# first.net
KiCad netlist of a schematic drawn in EasyEDA
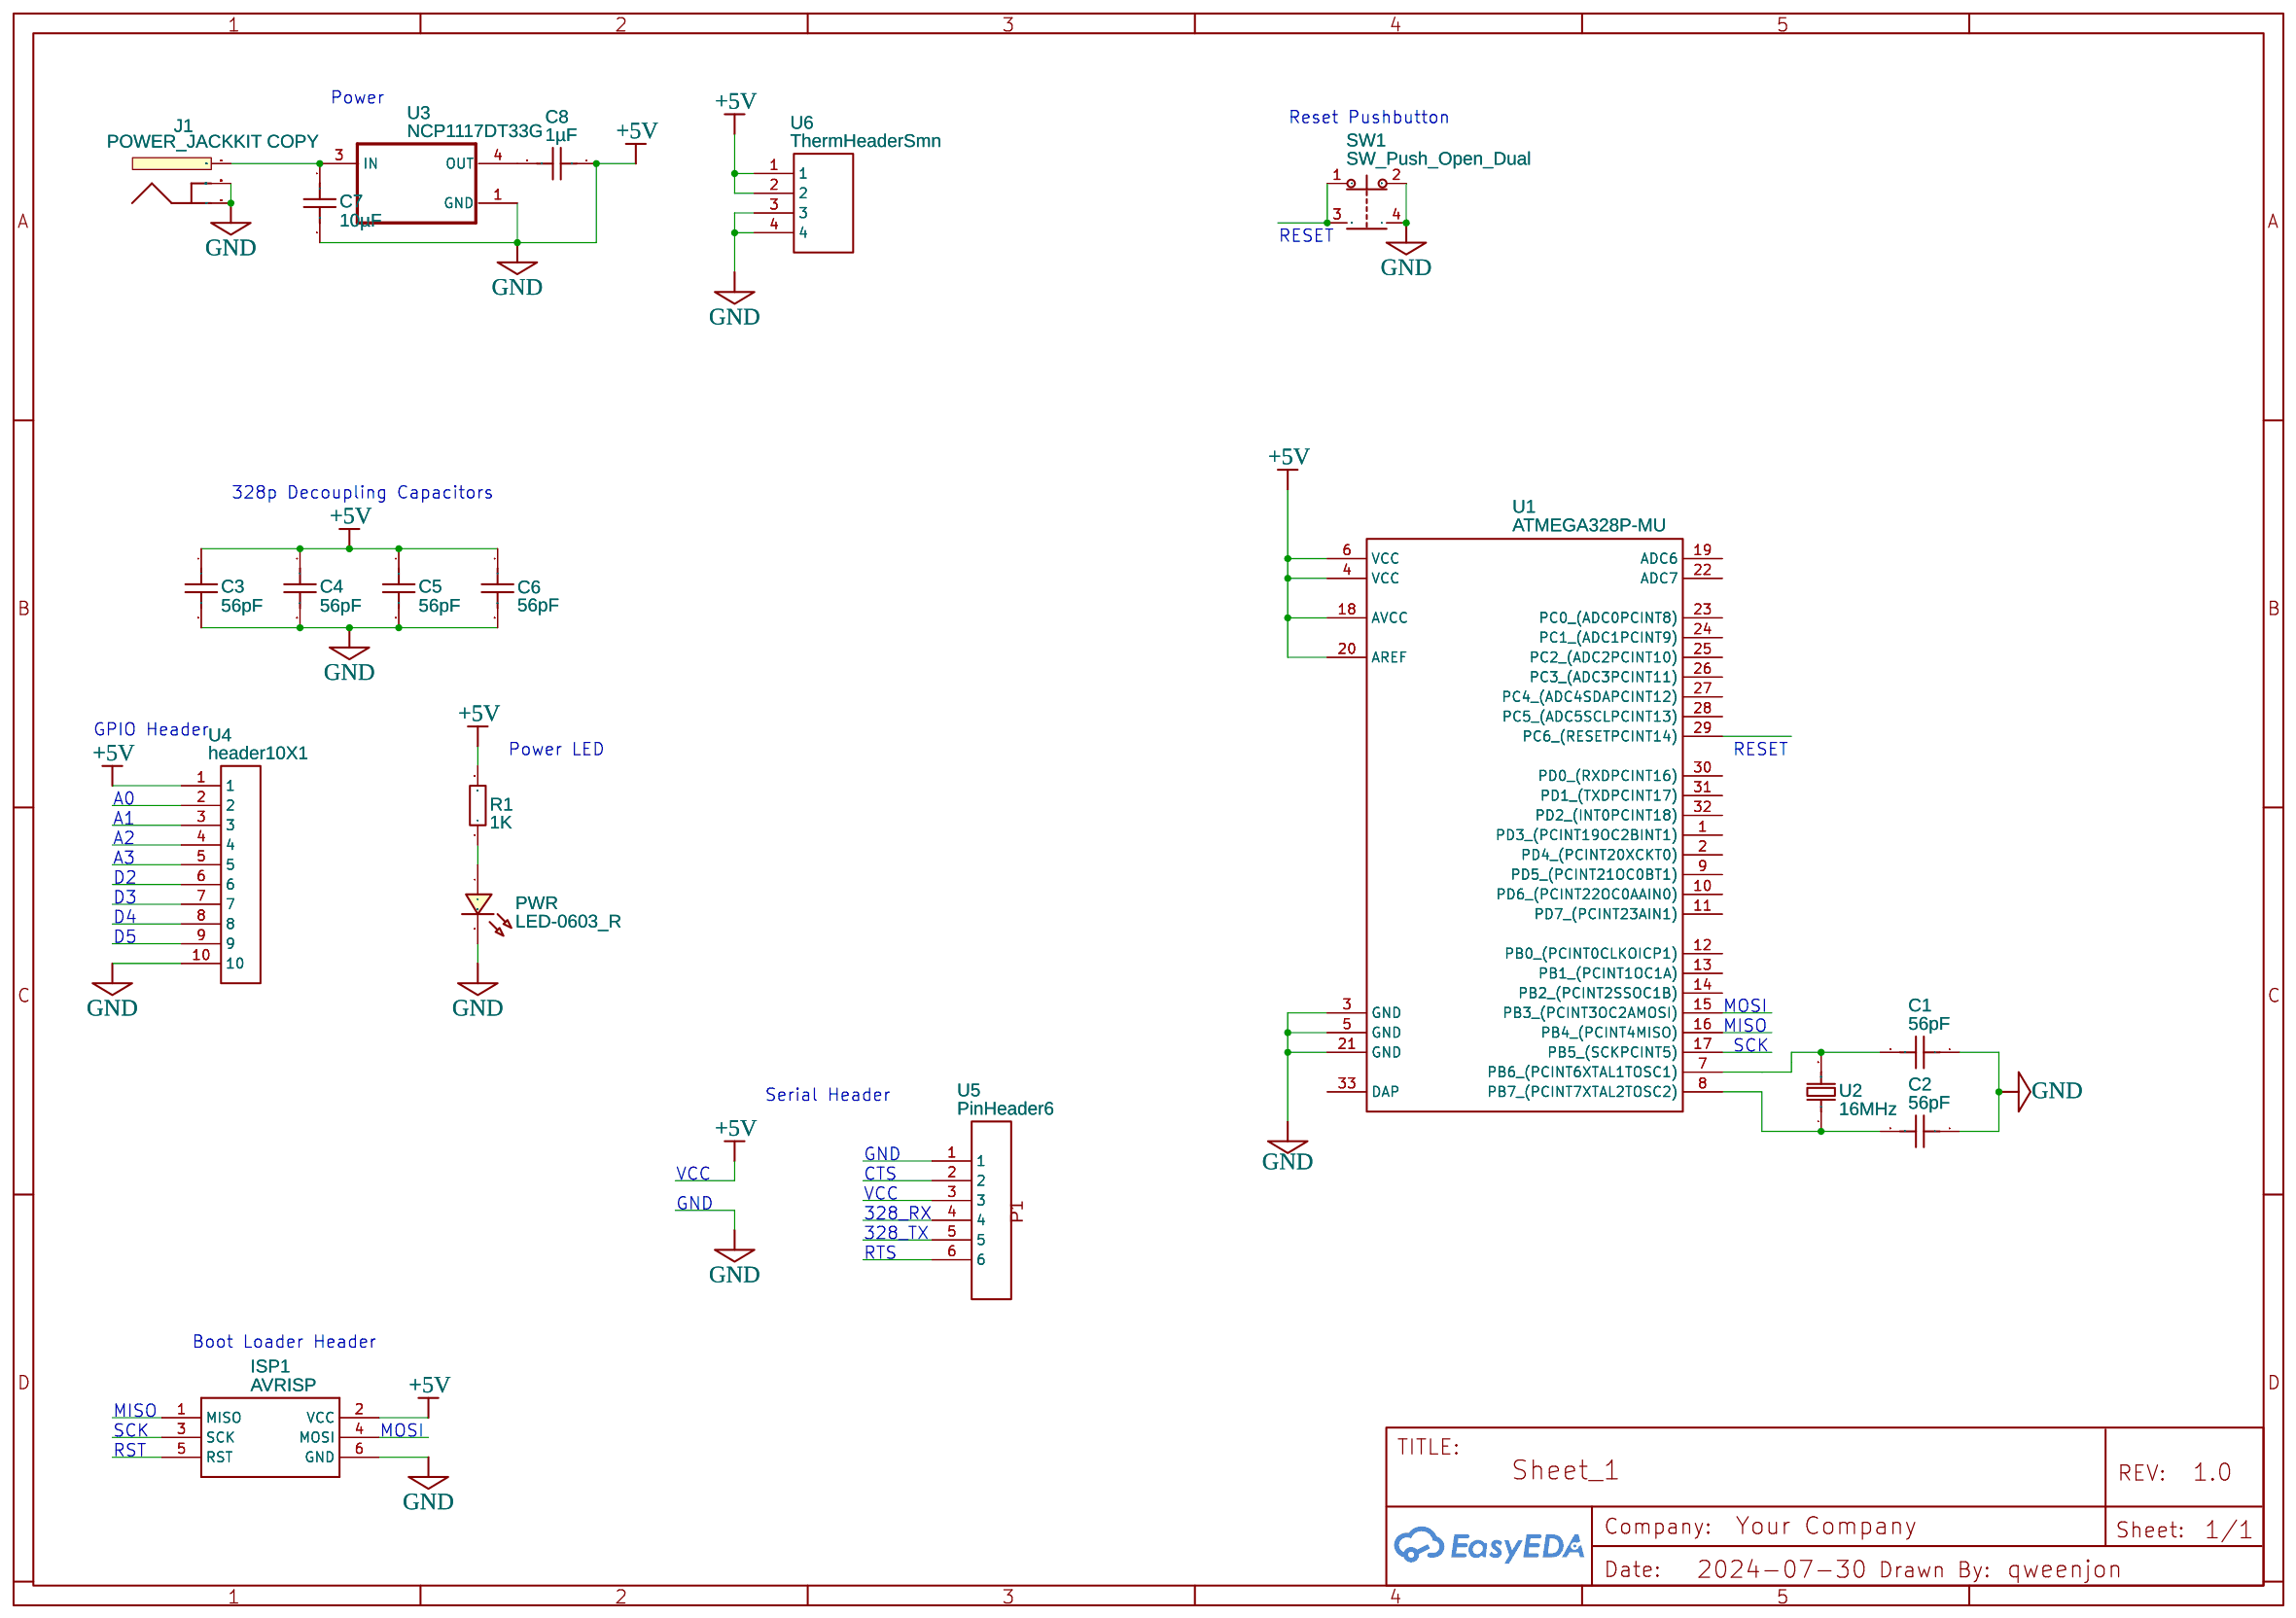
[diagram p0: schematic sheet]

(export (version "E")
  (design (tool "Eeschema 10.0.6"))
  (components
    (comp (ref "C1")
      (value "56pF")
      (fields
        (field (name "Manufacturer Part") "TCC0805COG560J101BT")
        (field (name "Manufacturer") "CCTC(三环)")
      )
      (libsource (lib "") (part "TCC0805C0G560J101BT_1"))
    )
    (comp (ref "C2")
      (value "56pF")
      (fields
        (field (name "Manufacturer Part") "TCC0805COG560J101BT")
        (field (name "Manufacturer") "CCTC(三环)")
      )
      (libsource (lib "") (part "TCC0805C0G560J101BT_1"))
    )
    (comp (ref "C3")
      (value "56pF")
      (fields
        (field (name "Manufacturer Part") "TCC0805COG560J101BT")
        (field (name "Manufacturer") "CCTC(三环)")
      )
      (libsource (lib "") (part "TCC0805C0G560J101BT"))
    )
    (comp (ref "C4")
      (value "56pF")
      (fields
        (field (name "Manufacturer Part") "TCC0805COG560J101BT")
        (field (name "Manufacturer") "CCTC(三环)")
      )
      (libsource (lib "") (part "TCC0805C0G560J101BT"))
    )
    (comp (ref "C5")
      (value "56pF")
      (fields
        (field (name "Manufacturer Part") "TCC0805COG560J101BT")
        (field (name "Manufacturer") "CCTC(三环)")
      )
      (libsource (lib "") (part "TCC0805C0G560J101BT"))
    )
    (comp (ref "C6")
      (value "56pF")
      (fields
        (field (name "Manufacturer Part") "TCC0805COG560J101BT")
        (field (name "Manufacturer") "CCTC(三环)")
      )
      (libsource (lib "") (part "TCC0805C0G560J101BT"))
    )
    (comp (ref "C7")
      (value "10µF")
      (fields
        (field (name "Manufacturer Part") "TCC0805COG560J101BT")
        (field (name "Manufacturer") "CCTC(三环)")
      )
      (libsource (lib "") (part "TCC0805C0G560J101BT"))
    )
    (comp (ref "C8")
      (value "1µF")
      (fields
        (field (name "Manufacturer Part") "TCC0805COG560J101BT")
        (field (name "Manufacturer") "CCTC(三环)")
      )
      (libsource (lib "") (part "TCC0805C0G560J101BT_1"))
    )
    (comp (ref "ISP1") (value "AVRISP") (libsource (lib "") (part "AVRISP")))
    (comp (ref "J1") (value "POWER_JACKKIT COPY") (libsource (lib "") (part "POWER_JACKKIT COPY")))
    (comp (ref "PWR")
      (value "LED-0603_R")
      (fields
        (field (name "Manufacturer Part") "19-217/R6C-AL1M2VY/3T")
        (field (name "Manufacturer") "EVERLIGHT(台湾亿光)")
      )
      (libsource (lib "") (part "LED-0603_R"))
    )
    (comp (ref "R1")
      (value "1K")
      (fields
        (field (name "Manufacturer Part") "PTFR0805B110RN9")
        (field (name "Manufacturer") "ResistorToday")
      )
      (libsource (lib "") (part "Resistor 0805"))
    )
    (comp (ref "SW1") (value "SW_Push_Open_Dual") (libsource (lib "") (part "SW_Push_Open_Dual")))
    (comp (ref "U1") (value "ATMEGA328P-MU") (libsource (lib "") (part "ATMEGA328P-MU")))
    (comp (ref "U2")
      (value "16MHz")
      (fields (field (name "Manufacturer Part") "EFO-PS5004E5") (field (name "Manufacturer") "PANASONIC(松下)"))
      (libsource (lib "") (part "EFO-PS5004E5"))
    )
    (comp (ref "U3") (value "NCP1117DT33G") (libsource (lib "") (part "NCP1117DT33G")))
    (comp (ref "U4") (value "header10X1") (libsource (lib "") (part "header10X1")))
    (comp (ref "U5") (value "PinHeader6") (libsource (lib "") (part "PinHeader6")))
    (comp (ref "U6") (value "ThermHeaderSmn") (libsource (lib "") (part "ThermHeaderSmn")))
  )
  (nets
    (net (code "1") (name "+5V") (class "Default")
      (node (ref "C1") (pin "1") (pinfunction "1_1") (pintype "unspecified"))
      (node (ref "C2") (pin "1") (pinfunction "1_1") (pintype "unspecified"))
      (node (ref "C3") (pin "1") (pinfunction "1_1") (pintype "unspecified"))
      (node (ref "C3") (pin "2") (pinfunction "2_2") (pintype "unspecified"))
      (node (ref "C4") (pin "1") (pinfunction "1_1") (pintype "unspecified"))
      (node (ref "C4") (pin "2") (pinfunction "2_2") (pintype "unspecified"))
      (node (ref "C5") (pin "1") (pinfunction "1_1") (pintype "unspecified"))
      (node (ref "C5") (pin "2") (pinfunction "2_2") (pintype "unspecified"))
      (node (ref "C6") (pin "1") (pinfunction "1_1") (pintype "unspecified"))
      (node (ref "C6") (pin "2") (pinfunction "2_2") (pintype "unspecified"))
      (node (ref "C7") (pin "2") (pinfunction "2_2") (pintype "unspecified"))
      (node (ref "C8") (pin "1") (pinfunction "1_1") (pintype "unspecified"))
      (node (ref "ISP1") (pin "2") (pinfunction "VCC_2") (pintype "passive"))
      (node (ref "ISP1") (pin "6") (pinfunction "GND_6") (pintype "passive"))
      (node (ref "J1") (pin "GND") (pinfunction "GND_GND") (pintype "bidirectional"))
      (node (ref "J1") (pin "GNDBREAK") (pinfunction "GNDBREAK_GNDBREAK") (pintype "bidirectional"))
      (node (ref "PWR") (pin "2") (pinfunction "2_2") (pintype "unspecified"))
      (node (ref "R1") (pin "2") (pinfunction "2_2") (pintype "unspecified"))
      (node (ref "SW1") (pin "2") (pinfunction "2_2") (pintype "unspecified"))
      (node (ref "SW1") (pin "4") (pinfunction "4_4") (pintype "unspecified"))
      (node (ref "U1") (pin "18") (pinfunction "AVCC_18") (pintype "passive"))
      (node (ref "U1") (pin "20") (pinfunction "AREF_20") (pintype "unspecified"))
      (node (ref "U1") (pin "21") (pinfunction "GND_21") (pintype "passive"))
      (node (ref "U1") (pin "3") (pinfunction "GND_3") (pintype "passive"))
      (node (ref "U1") (pin "4") (pinfunction "VCC_4") (pintype "passive"))
      (node (ref "U1") (pin "5") (pinfunction "GND_5") (pintype "passive"))
      (node (ref "U1") (pin "6") (pinfunction "VCC_6") (pintype "passive"))
      (node (ref "U3") (pin "1") (pinfunction "GND_1") (pintype "bidirectional"))
      (node (ref "U4") (pin "1") (pinfunction "1_1") (pintype "unspecified"))
      (node (ref "U4") (pin "10") (pinfunction "10_10") (pintype "unspecified"))
      (node (ref "U6") (pin "1") (pinfunction "1_1") (pintype "unspecified"))
      (node (ref "U6") (pin "2") (pinfunction "2_2") (pintype "unspecified"))
      (node (ref "U6") (pin "3") (pinfunction "3_3") (pintype "unspecified"))
      (node (ref "U6") (pin "4") (pinfunction "4_4") (pintype "unspecified"))
    )
    (net (code "2") (name "Net-(PWR-Pad1)") (class "Default")
      (node (ref "PWR") (pin "1") (pinfunction "1_1") (pintype "unspecified"))
      (node (ref "R1") (pin "1") (pinfunction "1_1") (pintype "unspecified"))
    )
    (net (code "3") (name "Net-(SW1-Pad1)") (class "Default")
      (node (ref "SW1") (pin "1") (pinfunction "1_1") (pintype "unspecified"))
      (node (ref "SW1") (pin "3") (pinfunction "3_3") (pintype "unspecified"))
    )
    (net (code "4") (name "Net-(U1-PB6_(PCINT6XTAL1TOSC1))") (class "Default")
      (node (ref "C1") (pin "2") (pinfunction "2_2") (pintype "unspecified"))
      (node (ref "U1") (pin "7") (pinfunction "PB6_(PCINT6XTAL1TOSC1)_7") (pintype "bidirectional"))
      (node (ref "U2") (pin "2") (pinfunction "2_2") (pintype "unspecified"))
    )
    (net (code "5") (name "Net-(U1-PB7_(PCINT7XTAL2TOSC2))") (class "Default")
      (node (ref "C2") (pin "2") (pinfunction "2_2") (pintype "unspecified"))
      (node (ref "U1") (pin "8") (pinfunction "PB7_(PCINT7XTAL2TOSC2)_8") (pintype "bidirectional"))
      (node (ref "U2") (pin "1") (pinfunction "1_1") (pintype "unspecified"))
    )
    (net (code "6") (name "Net-(U3-IN)") (class "Default")
      (node (ref "C7") (pin "1") (pinfunction "1_1") (pintype "unspecified"))
      (node (ref "J1") (pin "PWR") (pinfunction "PWR_PWR") (pintype "bidirectional"))
      (node (ref "U3") (pin "3") (pinfunction "IN_3") (pintype "bidirectional"))
    )
    (net (code "7") (name "Net-(U3-OUT)") (class "Default")
      (node (ref "C8") (pin "2") (pinfunction "2_2") (pintype "unspecified"))
      (node (ref "U3") (pin "4") (pinfunction "OUT_4") (pintype "bidirectional"))
    )
    (net (code "8") (name "unconnected-(ISP1-MISO-Pad1)") (class "Default")
      (node (ref "ISP1") (pin "1") (pinfunction "MISO_1") (pintype "input"))
    )
    (net (code "9") (name "unconnected-(ISP1-MOSI-Pad4)") (class "Default")
      (node (ref "ISP1") (pin "4") (pinfunction "MOSI_4") (pintype "output"))
    )
    (net (code "10") (name "unconnected-(ISP1-RST-Pad5)") (class "Default")
      (node (ref "ISP1") (pin "5") (pinfunction "RST_5") (pintype "output"))
    )
    (net (code "11") (name "unconnected-(ISP1-SCK-Pad3)") (class "Default")
      (node (ref "ISP1") (pin "3") (pinfunction "SCK_3") (pintype "output"))
    )
    (net (code "12") (name "unconnected-(U1-ADC6-Pad19)") (class "Default")
      (node (ref "U1") (pin "19") (pinfunction "ADC6_19") (pintype "unspecified"))
    )
    (net (code "13") (name "unconnected-(U1-ADC7-Pad22)") (class "Default")
      (node (ref "U1") (pin "22") (pinfunction "ADC7_22") (pintype "unspecified"))
    )
    (net (code "14") (name "unconnected-(U1-DAP-Pad33)") (class "Default")
      (node (ref "U1") (pin "33") (pinfunction "DAP_33") (pintype "passive"))
    )
    (net (code "15") (name "unconnected-(U1-PB0_(PCINT0CLKOICP1)-Pad12)") (class "Default")
      (node (ref "U1") (pin "12") (pinfunction "PB0_(PCINT0CLKOICP1)_12") (pintype "bidirectional"))
    )
    (net (code "16") (name "unconnected-(U1-PB1_(PCINT1OC1A)-Pad13)") (class "Default")
      (node (ref "U1") (pin "13") (pinfunction "PB1_(PCINT1OC1A)_13") (pintype "bidirectional"))
    )
    (net (code "17") (name "unconnected-(U1-PB2_(PCINT2SSOC1B)-Pad14)") (class "Default")
      (node (ref "U1") (pin "14") (pinfunction "PB2_(PCINT2SSOC1B)_14") (pintype "bidirectional"))
    )
    (net (code "18") (name "unconnected-(U1-PB3_(PCINT3OC2AMOSI)-Pad15)") (class "Default")
      (node (ref "U1") (pin "15") (pinfunction "PB3_(PCINT3OC2AMOSI)_15") (pintype "bidirectional"))
    )
    (net (code "19") (name "unconnected-(U1-PB4_(PCINT4MISO)-Pad16)") (class "Default")
      (node (ref "U1") (pin "16") (pinfunction "PB4_(PCINT4MISO)_16") (pintype "bidirectional"))
    )
    (net (code "20") (name "unconnected-(U1-PB5_(SCKPCINT5)-Pad17)") (class "Default")
      (node (ref "U1") (pin "17") (pinfunction "PB5_(SCKPCINT5)_17") (pintype "bidirectional"))
    )
    (net (code "21") (name "unconnected-(U1-PC0_(ADC0PCINT8)-Pad23)") (class "Default")
      (node (ref "U1") (pin "23") (pinfunction "PC0_(ADC0PCINT8)_23") (pintype "bidirectional"))
    )
    (net (code "22") (name "unconnected-(U1-PC1_(ADC1PCINT9)-Pad24)") (class "Default")
      (node (ref "U1") (pin "24") (pinfunction "PC1_(ADC1PCINT9)_24") (pintype "bidirectional"))
    )
    (net (code "23") (name "unconnected-(U1-PC2_(ADC2PCINT10)-Pad25)") (class "Default")
      (node (ref "U1") (pin "25") (pinfunction "PC2_(ADC2PCINT10)_25") (pintype "bidirectional"))
    )
    (net (code "24") (name "unconnected-(U1-PC3_(ADC3PCINT11)-Pad26)") (class "Default")
      (node (ref "U1") (pin "26") (pinfunction "PC3_(ADC3PCINT11)_26") (pintype "bidirectional"))
    )
    (net (code "25") (name "unconnected-(U1-PC4_(ADC4SDAPCINT12)-Pad27)") (class "Default")
      (node (ref "U1") (pin "27") (pinfunction "PC4_(ADC4SDAPCINT12)_27") (pintype "bidirectional"))
    )
    (net (code "26") (name "unconnected-(U1-PC5_(ADC5SCLPCINT13)-Pad28)") (class "Default")
      (node (ref "U1") (pin "28") (pinfunction "PC5_(ADC5SCLPCINT13)_28") (pintype "bidirectional"))
    )
    (net (code "27") (name "unconnected-(U1-PC6_(RESETPCINT14)-Pad29)") (class "Default")
      (node (ref "U1") (pin "29") (pinfunction "PC6_(RESETPCINT14)_29") (pintype "bidirectional"))
    )
    (net (code "28") (name "unconnected-(U1-PD0_(RXDPCINT16)-Pad30)") (class "Default")
      (node (ref "U1") (pin "30") (pinfunction "PD0_(RXDPCINT16)_30") (pintype "bidirectional"))
    )
    (net (code "29") (name "unconnected-(U1-PD1_(TXDPCINT17)-Pad31)") (class "Default")
      (node (ref "U1") (pin "31") (pinfunction "PD1_(TXDPCINT17)_31") (pintype "bidirectional"))
    )
    (net (code "30") (name "unconnected-(U1-PD2_(INT0PCINT18)-Pad32)") (class "Default")
      (node (ref "U1") (pin "32") (pinfunction "PD2_(INT0PCINT18)_32") (pintype "bidirectional"))
    )
    (net (code "31") (name "unconnected-(U1-PD3_(PCINT19OC2BINT1)-Pad1)") (class "Default")
      (node (ref "U1") (pin "1") (pinfunction "PD3_(PCINT19OC2BINT1)_1") (pintype "bidirectional"))
    )
    (net (code "32") (name "unconnected-(U1-PD4_(PCINT20XCKT0)-Pad2)") (class "Default")
      (node (ref "U1") (pin "2") (pinfunction "PD4_(PCINT20XCKT0)_2") (pintype "bidirectional"))
    )
    (net (code "33") (name "unconnected-(U1-PD5_(PCINT21OC0BT1)-Pad9)") (class "Default")
      (node (ref "U1") (pin "9") (pinfunction "PD5_(PCINT21OC0BT1)_9") (pintype "bidirectional"))
    )
    (net (code "34") (name "unconnected-(U1-PD6_(PCINT22OC0AAIN0)-Pad10)") (class "Default")
      (node (ref "U1") (pin "10") (pinfunction "PD6_(PCINT22OC0AAIN0)_10") (pintype "bidirectional"))
    )
    (net (code "35") (name "unconnected-(U1-PD7_(PCINT23AIN1)-Pad11)") (class "Default")
      (node (ref "U1") (pin "11") (pinfunction "PD7_(PCINT23AIN1)_11") (pintype "bidirectional"))
    )
    (net (code "36") (name "unconnected-(U4-Pad2)") (class "Default")
      (node (ref "U4") (pin "2") (pinfunction "2_2") (pintype "unspecified"))
    )
    (net (code "37") (name "unconnected-(U4-Pad3)") (class "Default")
      (node (ref "U4") (pin "3") (pinfunction "3_3") (pintype "unspecified"))
    )
    (net (code "38") (name "unconnected-(U4-Pad4)") (class "Default")
      (node (ref "U4") (pin "4") (pinfunction "4_4") (pintype "unspecified"))
    )
    (net (code "39") (name "unconnected-(U4-Pad5)") (class "Default")
      (node (ref "U4") (pin "5") (pinfunction "5_5") (pintype "unspecified"))
    )
    (net (code "40") (name "unconnected-(U4-Pad6)") (class "Default")
      (node (ref "U4") (pin "6") (pinfunction "6_6") (pintype "unspecified"))
    )
    (net (code "41") (name "unconnected-(U4-Pad7)") (class "Default")
      (node (ref "U4") (pin "7") (pinfunction "7_7") (pintype "unspecified"))
    )
    (net (code "42") (name "unconnected-(U4-Pad8)") (class "Default")
      (node (ref "U4") (pin "8") (pinfunction "8_8") (pintype "unspecified"))
    )
    (net (code "43") (name "unconnected-(U4-Pad9)") (class "Default")
      (node (ref "U4") (pin "9") (pinfunction "9_9") (pintype "unspecified"))
    )
    (net (code "44") (name "unconnected-(U5-Pad1)") (class "Default")
      (node (ref "U5") (pin "1") (pinfunction "1_1") (pintype "unspecified"))
    )
    (net (code "45") (name "unconnected-(U5-Pad2)") (class "Default")
      (node (ref "U5") (pin "2") (pinfunction "2_2") (pintype "unspecified"))
    )
    (net (code "46") (name "unconnected-(U5-Pad3)") (class "Default")
      (node (ref "U5") (pin "3") (pinfunction "3_3") (pintype "unspecified"))
    )
    (net (code "47") (name "unconnected-(U5-Pad4)") (class "Default")
      (node (ref "U5") (pin "4") (pinfunction "4_4") (pintype "unspecified"))
    )
    (net (code "48") (name "unconnected-(U5-Pad5)") (class "Default")
      (node (ref "U5") (pin "5") (pinfunction "5_5") (pintype "unspecified"))
    )
    (net (code "49") (name "unconnected-(U5-Pad6)") (class "Default")
      (node (ref "U5") (pin "6") (pinfunction "6_6") (pintype "unspecified"))
    )
  )
)
